# USB_hub.net
KiCad netlist of a schematic drawn in Altium Designer
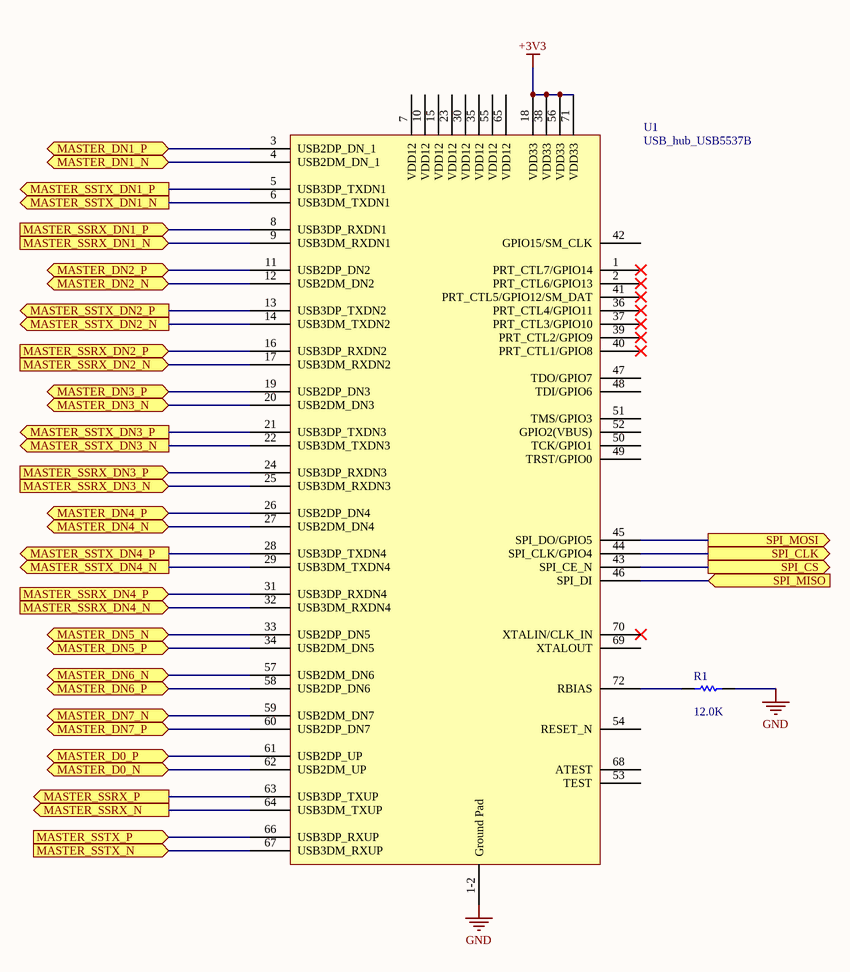
[diagram p0: USB_hub.SchDoc]

(export (version "E")
  (design (tool "Eeschema 10.0.6"))
  (components
    (comp (ref "R1")
      (value "12.0K")
      (footprint "Miscellaneous Devices:RESC6332")
      (description "Resistor")
      (fields (field (name "Comment") "Res1") (field (name "PUBLISHER") "Altium Limited"))
      (libsource (lib "RSX_Resistors") (part "Res1"))
    )
    (comp (ref "U1")
      (value "USB_hub_USB5537B")
      (footprint "QFN50P1000X1000X100_HS-73N")
      (description "https://media.digikey.com/pdf/Data%20Sheets/Microchip%20PDFs/USB5537B.pdf")
      (libsource (lib "Backplane_Board") (part "USB_hub_USB5537B"))
    )
  )
  (nets
    (net (code "1") (name "+3V3") (class "Default")
      (node (ref "U1") (pin "18") (pinfunction "VDD33_18") (pintype "passive"))
      (node (ref "U1") (pin "38") (pinfunction "VDD33_38") (pintype "passive"))
      (node (ref "U1") (pin "56") (pinfunction "VDD33_56") (pintype "passive"))
      (node (ref "U1") (pin "71") (pinfunction "VDD33_71") (pintype "passive"))
    )
    (net (code "2") (name "/MASTER_D0_N") (class "Default")
      (node (ref "U1") (pin "62") (pinfunction "USB2DM_UP_62") (pintype "passive"))
    )
    (net (code "3") (name "/MASTER_D0_P") (class "Default")
      (node (ref "U1") (pin "61") (pinfunction "USB2DP_UP_61") (pintype "passive"))
    )
    (net (code "4") (name "/MASTER_DN1_N") (class "Default")
      (node (ref "U1") (pin "4") (pinfunction "USB2DM_DN_1_4") (pintype "passive"))
    )
    (net (code "5") (name "/MASTER_DN1_P") (class "Default")
      (node (ref "U1") (pin "3") (pinfunction "USB2DP_DN_1_3") (pintype "passive"))
    )
    (net (code "6") (name "/MASTER_DN2_N") (class "Default")
      (node (ref "U1") (pin "12") (pinfunction "USB2DM_DN2_12") (pintype "passive"))
    )
    (net (code "7") (name "/MASTER_DN2_P") (class "Default")
      (node (ref "U1") (pin "11") (pinfunction "USB2DP_DN2_11") (pintype "passive"))
    )
    (net (code "8") (name "/MASTER_DN3_N") (class "Default")
      (node (ref "U1") (pin "20") (pinfunction "USB2DM_DN3_20") (pintype "passive"))
    )
    (net (code "9") (name "/MASTER_DN3_P") (class "Default")
      (node (ref "U1") (pin "19") (pinfunction "USB2DP_DN3_19") (pintype "passive"))
    )
    (net (code "10") (name "/MASTER_DN4_N") (class "Default")
      (node (ref "U1") (pin "27") (pinfunction "USB2DM_DN4_27") (pintype "passive"))
    )
    (net (code "11") (name "/MASTER_DN4_P") (class "Default")
      (node (ref "U1") (pin "26") (pinfunction "USB2DP_DN4_26") (pintype "passive"))
    )
    (net (code "12") (name "/MASTER_DN5_N") (class "Default")
      (node (ref "U1") (pin "33") (pinfunction "USB2DP_DN5_33") (pintype "passive"))
    )
    (net (code "13") (name "/MASTER_DN5_P") (class "Default")
      (node (ref "U1") (pin "34") (pinfunction "USB2DM_DN5_34") (pintype "passive"))
    )
    (net (code "14") (name "/MASTER_DN6_N") (class "Default")
      (node (ref "U1") (pin "57") (pinfunction "USB2DM_DN6_57") (pintype "passive"))
    )
    (net (code "15") (name "/MASTER_DN6_P") (class "Default")
      (node (ref "U1") (pin "58") (pinfunction "USB2DP_DN6_58") (pintype "passive"))
    )
    (net (code "16") (name "/MASTER_DN7_N") (class "Default")
      (node (ref "U1") (pin "59") (pinfunction "USB2DM_DN7_59") (pintype "passive"))
    )
    (net (code "17") (name "/MASTER_DN7_P") (class "Default")
      (node (ref "U1") (pin "60") (pinfunction "USB2DP_DN7_60") (pintype "passive"))
    )
    (net (code "18") (name "/MASTER_SSRX_DN1_N") (class "Default")
      (node (ref "U1") (pin "9") (pinfunction "USB3DM_RXDN1_9") (pintype "passive"))
    )
    (net (code "19") (name "/MASTER_SSRX_DN1_P") (class "Default")
      (node (ref "U1") (pin "8") (pinfunction "USB3DP_RXDN1_8") (pintype "passive"))
    )
    (net (code "20") (name "/MASTER_SSRX_DN2_N") (class "Default")
      (node (ref "U1") (pin "17") (pinfunction "USB3DM_RXDN2_17") (pintype "passive"))
    )
    (net (code "21") (name "/MASTER_SSRX_DN2_P") (class "Default")
      (node (ref "U1") (pin "16") (pinfunction "USB3DP_RXDN2_16") (pintype "passive"))
    )
    (net (code "22") (name "/MASTER_SSRX_DN3_N") (class "Default")
      (node (ref "U1") (pin "25") (pinfunction "USB3DM_RXDN3_25") (pintype "passive"))
    )
    (net (code "23") (name "/MASTER_SSRX_DN3_P") (class "Default")
      (node (ref "U1") (pin "24") (pinfunction "USB3DP_RXDN3_24") (pintype "passive"))
    )
    (net (code "24") (name "/MASTER_SSRX_DN4_N") (class "Default")
      (node (ref "U1") (pin "32") (pinfunction "USB3DM_RXDN4_32") (pintype "passive"))
    )
    (net (code "25") (name "/MASTER_SSRX_DN4_P") (class "Default")
      (node (ref "U1") (pin "31") (pinfunction "USB3DP_RXDN4_31") (pintype "passive"))
    )
    (net (code "26") (name "/MASTER_SSRX_N") (class "Default")
      (node (ref "U1") (pin "64") (pinfunction "USB3DM_TXUP_64") (pintype "passive"))
    )
    (net (code "27") (name "/MASTER_SSRX_P") (class "Default")
      (node (ref "U1") (pin "63") (pinfunction "USB3DP_TXUP_63") (pintype "passive"))
    )
    (net (code "28") (name "/MASTER_SSTX_DN1_N") (class "Default")
      (node (ref "U1") (pin "6") (pinfunction "USB3DM_TXDN1_6") (pintype "passive"))
    )
    (net (code "29") (name "/MASTER_SSTX_DN1_P") (class "Default")
      (node (ref "U1") (pin "5") (pinfunction "USB3DP_TXDN1_5") (pintype "passive"))
    )
    (net (code "30") (name "/MASTER_SSTX_DN2_N") (class "Default")
      (node (ref "U1") (pin "14") (pinfunction "USB3DM_TXDN2_14") (pintype "passive"))
    )
    (net (code "31") (name "/MASTER_SSTX_DN2_P") (class "Default")
      (node (ref "U1") (pin "13") (pinfunction "USB3DP_TXDN2_13") (pintype "passive"))
    )
    (net (code "32") (name "/MASTER_SSTX_DN3_N") (class "Default")
      (node (ref "U1") (pin "22") (pinfunction "USB3DM_TXDN3_22") (pintype "passive"))
    )
    (net (code "33") (name "/MASTER_SSTX_DN3_P") (class "Default")
      (node (ref "U1") (pin "21") (pinfunction "USB3DP_TXDN3_21") (pintype "passive"))
    )
    (net (code "34") (name "/MASTER_SSTX_DN4_N") (class "Default")
      (node (ref "U1") (pin "29") (pinfunction "USB3DM_TXDN4_29") (pintype "passive"))
    )
    (net (code "35") (name "/MASTER_SSTX_DN4_P") (class "Default")
      (node (ref "U1") (pin "28") (pinfunction "USB3DP_TXDN4_28") (pintype "passive"))
    )
    (net (code "36") (name "/MASTER_SSTX_N") (class "Default")
      (node (ref "U1") (pin "67") (pinfunction "USB3DM_RXUP_67") (pintype "passive"))
    )
    (net (code "37") (name "/MASTER_SSTX_P") (class "Default")
      (node (ref "U1") (pin "66") (pinfunction "USB3DP_RXUP_66") (pintype "passive"))
    )
    (net (code "38") (name "/SPI_CLK") (class "Default")
      (node (ref "U1") (pin "44") (pinfunction "SPI_CLK/GPIO4_44") (pintype "passive"))
    )
    (net (code "39") (name "/SPI_CS") (class "Default")
      (node (ref "U1") (pin "43") (pinfunction "SPI_CE_N_43") (pintype "passive"))
    )
    (net (code "40") (name "/SPI_MISO") (class "Default")
      (node (ref "U1") (pin "46") (pinfunction "SPI_DI_46") (pintype "passive"))
    )
    (net (code "41") (name "/SPI_MOSI") (class "Default")
      (node (ref "U1") (pin "45") (pinfunction "SPI_DO/GPIO5_45") (pintype "passive"))
    )
    (net (code "42") (name "GND") (class "Default")
      (node (ref "R1") (pin "2") (pinfunction "2_2") (pintype "passive"))
      (node (ref "U1") (pin "1-2") (pinfunction "Ground_Pad_1-2") (pintype "passive"))
    )
    (net (code "43") (name "Net-(U1-RBIAS)") (class "Default")
      (node (ref "R1") (pin "1") (pinfunction "1_1") (pintype "passive"))
      (node (ref "U1") (pin "72") (pinfunction "RBIAS_72") (pintype "passive"))
    )
    (net (code "44") (name "unconnected-(U1-ATEST-Pad68)") (class "Default")
      (node (ref "U1") (pin "68") (pinfunction "ATEST_68") (pintype "passive"))
    )
    (net (code "45") (name "unconnected-(U1-GPIO2(VBUS)-Pad52)") (class "Default")
      (node (ref "U1") (pin "52") (pinfunction "GPIO2(VBUS)_52") (pintype "passive"))
    )
    (net (code "46") (name "unconnected-(U1-GPIO15{slash}SM_CLK-Pad42)") (class "Default")
      (node (ref "U1") (pin "42") (pinfunction "GPIO15/SM_CLK_42") (pintype "passive"))
    )
    (net (code "47") (name "unconnected-(U1-PRT_CTL1{slash}GPIO8-Pad40)") (class "Default")
      (node (ref "U1") (pin "40") (pinfunction "PRT_CTL1/GPIO8_40") (pintype "passive+no_connect"))
    )
    (net (code "48") (name "unconnected-(U1-PRT_CTL2{slash}GPIO9-Pad39)") (class "Default")
      (node (ref "U1") (pin "39") (pinfunction "PRT_CTL2/GPIO9_39") (pintype "passive+no_connect"))
    )
    (net (code "49") (name "unconnected-(U1-PRT_CTL3{slash}GPIO10-Pad37)") (class "Default")
      (node (ref "U1") (pin "37") (pinfunction "PRT_CTL3/GPIO10_37") (pintype "passive+no_connect"))
    )
    (net (code "50") (name "unconnected-(U1-PRT_CTL4{slash}GPIO11-Pad36)") (class "Default")
      (node (ref "U1") (pin "36") (pinfunction "PRT_CTL4/GPIO11_36") (pintype "passive+no_connect"))
    )
    (net (code "51") (name "unconnected-(U1-PRT_CTL5{slash}GPIO12{slash}SM_DAT-Pad41)") (class "Default")
      (node (ref "U1") (pin "41") (pinfunction "PRT_CTL5/GPIO12/SM_DAT_41") (pintype "passive+no_connect"))
    )
    (net (code "52") (name "unconnected-(U1-PRT_CTL6{slash}GPIO13-Pad2)") (class "Default")
      (node (ref "U1") (pin "2") (pinfunction "PRT_CTL6/GPIO13_2") (pintype "passive+no_connect"))
    )
    (net (code "53") (name "unconnected-(U1-PRT_CTL7{slash}GPIO14-Pad1)") (class "Default")
      (node (ref "U1") (pin "1") (pinfunction "PRT_CTL7/GPIO14_1") (pintype "passive+no_connect"))
    )
    (net (code "54") (name "unconnected-(U1-RESET_N-Pad54)") (class "Default")
      (node (ref "U1") (pin "54") (pinfunction "RESET_N_54") (pintype "passive"))
    )
    (net (code "55") (name "unconnected-(U1-TCK{slash}GPIO1-Pad50)") (class "Default")
      (node (ref "U1") (pin "50") (pinfunction "TCK/GPIO1_50") (pintype "passive"))
    )
    (net (code "56") (name "unconnected-(U1-TDI{slash}GPIO6-Pad48)") (class "Default")
      (node (ref "U1") (pin "48") (pinfunction "TDI/GPIO6_48") (pintype "passive"))
    )
    (net (code "57") (name "unconnected-(U1-TDO{slash}GPIO7-Pad47)") (class "Default")
      (node (ref "U1") (pin "47") (pinfunction "TDO/GPIO7_47") (pintype "passive"))
    )
    (net (code "58") (name "unconnected-(U1-TEST-Pad53)") (class "Default")
      (node (ref "U1") (pin "53") (pinfunction "TEST_53") (pintype "passive"))
    )
    (net (code "59") (name "unconnected-(U1-TMS{slash}GPIO3-Pad51)") (class "Default")
      (node (ref "U1") (pin "51") (pinfunction "TMS/GPIO3_51") (pintype "passive"))
    )
    (net (code "60") (name "unconnected-(U1-TRST{slash}GPIO0-Pad49)") (class "Default")
      (node (ref "U1") (pin "49") (pinfunction "TRST/GPIO0_49") (pintype "passive"))
    )
    (net (code "61") (name "unconnected-(U1-VDD12-Pad7)") (class "Default")
      (node (ref "U1") (pin "7") (pinfunction "VDD12_7") (pintype "passive"))
    )
    (net (code "62") (name "unconnected-(U1-VDD12-Pad10)") (class "Default")
      (node (ref "U1") (pin "10") (pinfunction "VDD12_10") (pintype "passive"))
    )
    (net (code "63") (name "unconnected-(U1-VDD12-Pad15)") (class "Default")
      (node (ref "U1") (pin "15") (pinfunction "VDD12_15") (pintype "passive"))
    )
    (net (code "64") (name "unconnected-(U1-VDD12-Pad23)") (class "Default")
      (node (ref "U1") (pin "23") (pinfunction "VDD12_23") (pintype "passive"))
    )
    (net (code "65") (name "unconnected-(U1-VDD12-Pad30)") (class "Default")
      (node (ref "U1") (pin "30") (pinfunction "VDD12_30") (pintype "passive"))
    )
    (net (code "66") (name "unconnected-(U1-VDD12-Pad35)") (class "Default")
      (node (ref "U1") (pin "35") (pinfunction "VDD12_35") (pintype "passive"))
    )
    (net (code "67") (name "unconnected-(U1-VDD12-Pad55)") (class "Default")
      (node (ref "U1") (pin "55") (pinfunction "VDD12_55") (pintype "passive"))
    )
    (net (code "68") (name "unconnected-(U1-VDD12-Pad65)") (class "Default")
      (node (ref "U1") (pin "65") (pinfunction "VDD12_65") (pintype "passive"))
    )
    (net (code "69") (name "unconnected-(U1-XTALIN{slash}CLK_IN-Pad70)") (class "Default")
      (node (ref "U1") (pin "70") (pinfunction "XTALIN/CLK_IN_70") (pintype "passive+no_connect"))
    )
    (net (code "70") (name "unconnected-(U1-XTALOUT-Pad69)") (class "Default")
      (node (ref "U1") (pin "69") (pinfunction "XTALOUT_69") (pintype "passive"))
    )
  )
)
